# radio_r3.net
KiCad netlist of a schematic drawn in EAGLE
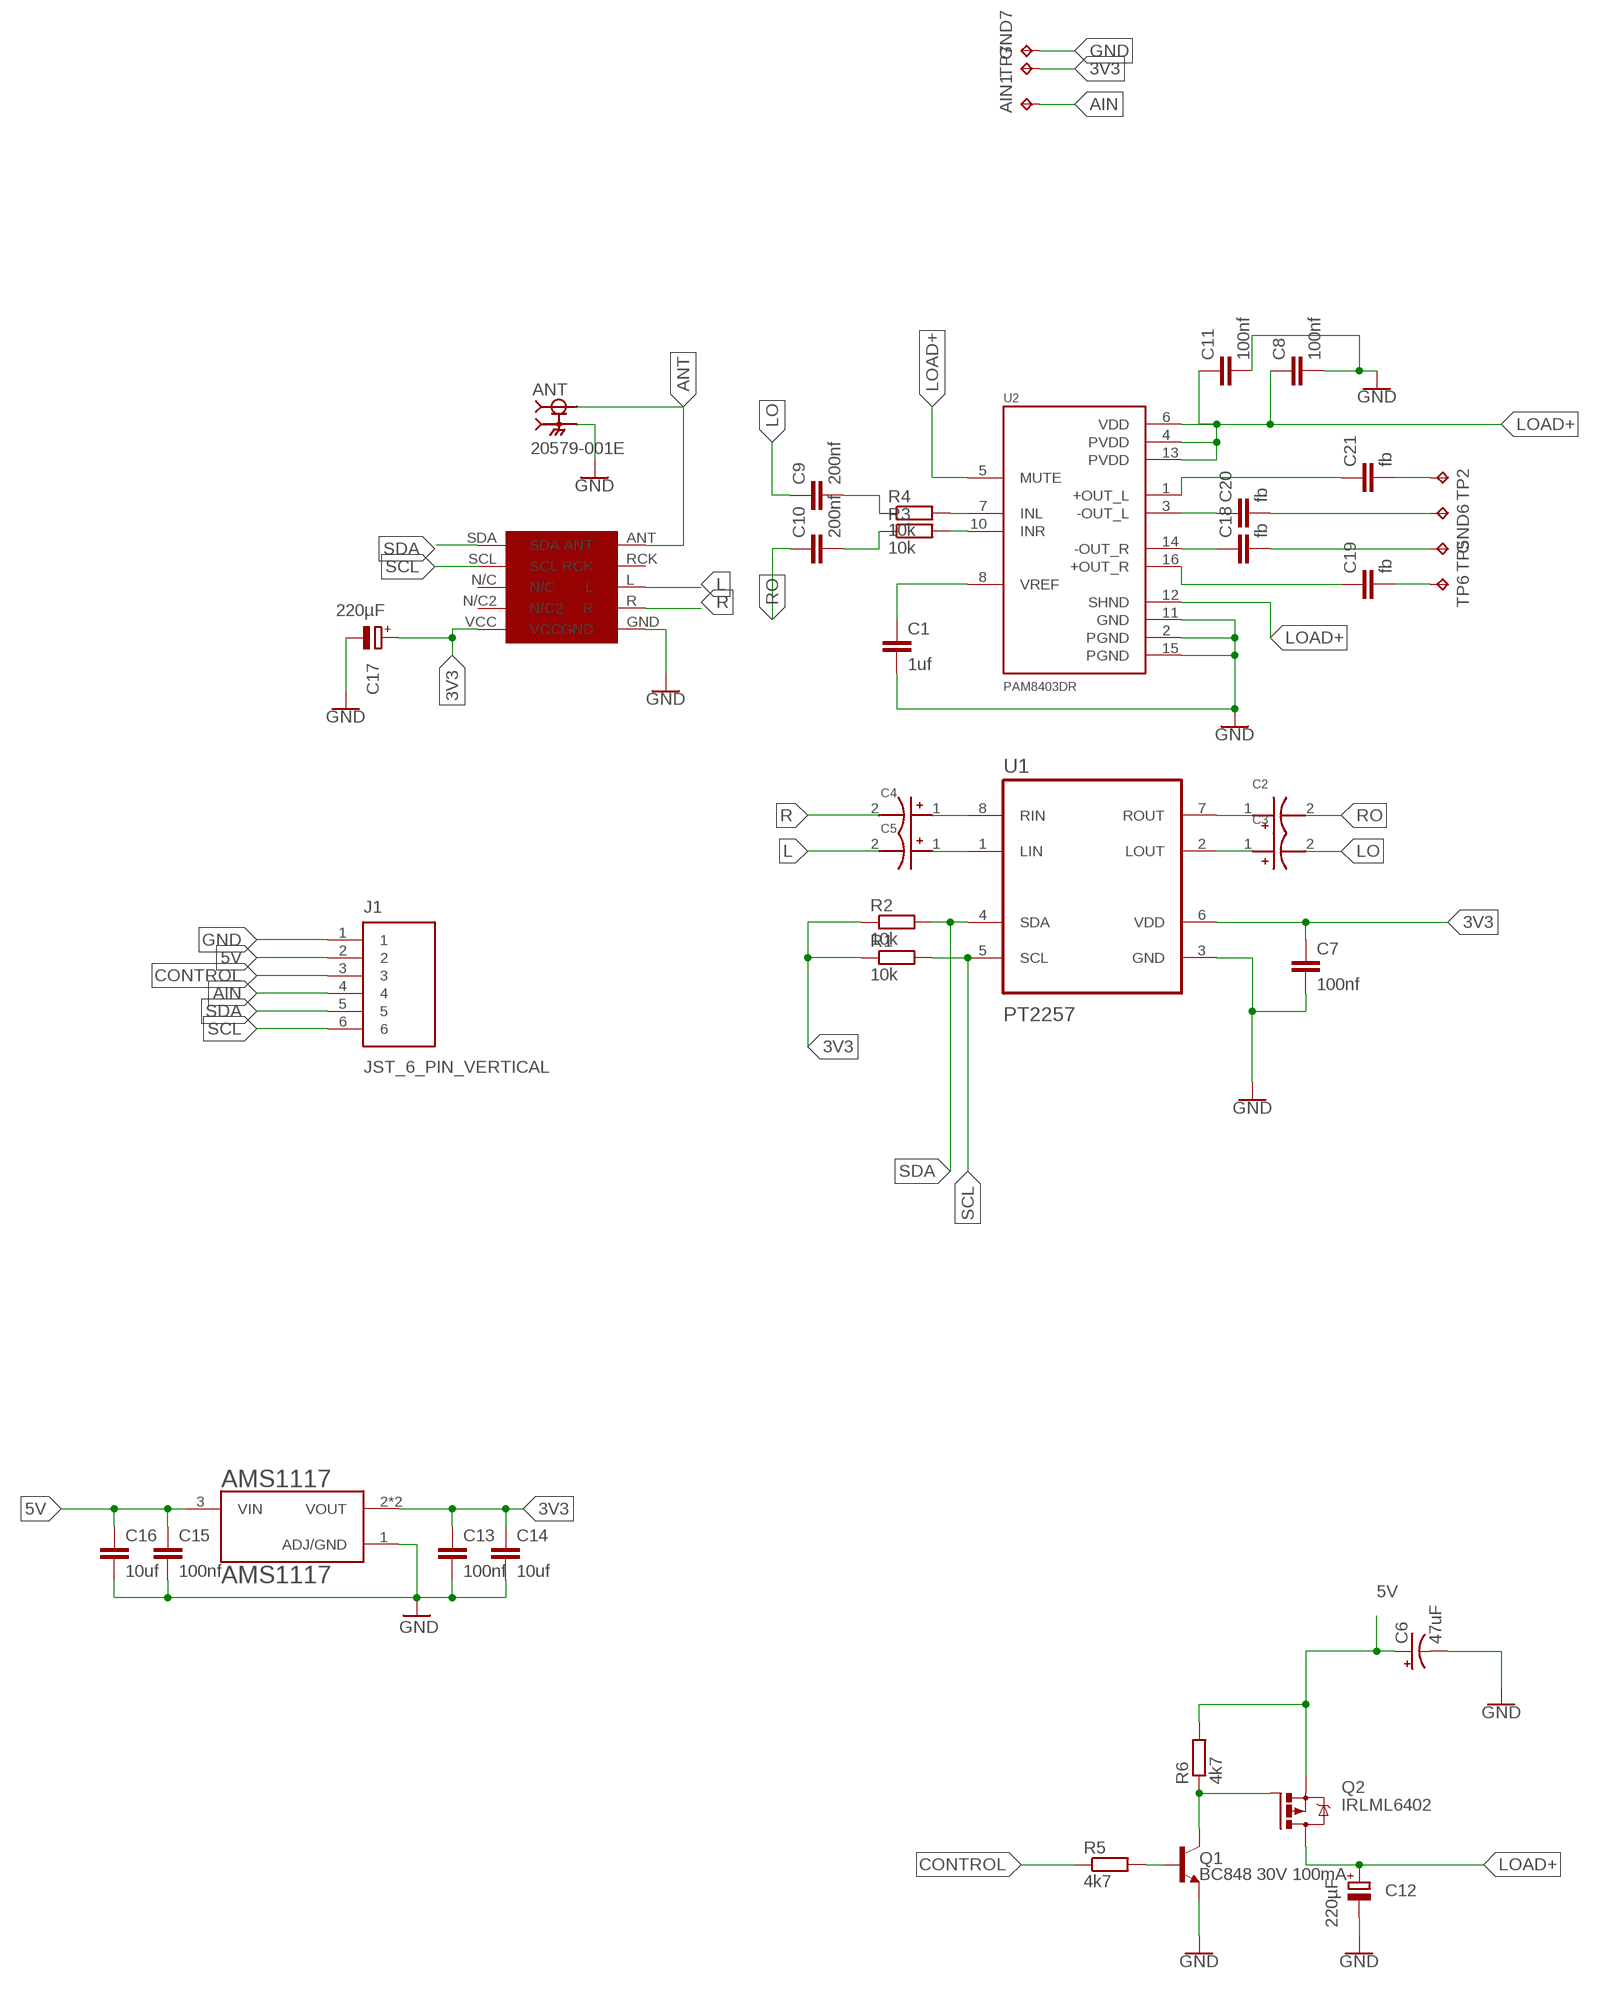
[diagram p0: schematic, sheet 1]

(export (version "E")
  (design (tool "Eeschema 10.0.6"))
  (components
    (comp (ref "AIN1")
      (value "TPTP10SQ")
      (footprint "eagle-import:TP10SQ")
      (libsource (lib "eagle-import") (part "TPTP10SQ"))
    )
    (comp (ref "AMS1117")
      (value "AMS1117")
      (footprint "eagle-import:SOT229P700X180-4N")
      (fields (field (name "MF") "Advanced Monolithic Systems"))
      (libsource (lib "eagle-import") (part "AMS1117"))
    )
    (comp (ref "ANT")
      (value "20579-001E")
      (footprint "eagle-import:IPEX_20579-001E")
      (fields (field (name "MF") "I-PEX"))
      (libsource (lib "eagle-import") (part "20579-001E"))
    )
    (comp (ref "C1")
      (value "1uf")
      (footprint "eagle-import:C0805")
      (libsource (lib "eagle-import") (part "C-EUC0805"))
    )
    (comp (ref "C2")
      (value "10uf")
      (footprint "eagle-import:CAPMP3216X180N")
      (fields (field (name "MF") "AVX") (field (name "MP") "TAJA106M010RNJ"))
      (libsource (lib "eagle-import") (part "TAJA106M010RNJ"))
    )
    (comp (ref "C3")
      (value "10uf")
      (footprint "eagle-import:CAPMP3216X180N")
      (fields (field (name "MF") "AVX") (field (name "MP") "TAJA106M010RNJ"))
      (libsource (lib "eagle-import") (part "TAJA106M010RNJ"))
    )
    (comp (ref "C4")
      (value "10uf")
      (footprint "eagle-import:CAPMP3216X180N")
      (fields (field (name "MF") "AVX") (field (name "MP") "TAJA106M010RNJ"))
      (libsource (lib "eagle-import") (part "TAJA106M010RNJ"))
    )
    (comp (ref "C5")
      (value "10uf")
      (footprint "eagle-import:CAPMP3216X180N")
      (fields (field (name "MF") "AVX") (field (name "MP") "TAJA106M010RNJ"))
      (libsource (lib "eagle-import") (part "TAJA106M010RNJ"))
    )
    (comp (ref "C6")
      (value "47uF")
      (footprint "eagle-import:EIA3528")
      (libsource (lib "eagle-import") (part "47UF-POLAR-EIA3528-10V-10%"))
    )
    (comp (ref "C7")
      (value "100nf")
      (footprint "eagle-import:C0603")
      (libsource (lib "eagle-import") (part "C-EUC0603"))
    )
    (comp (ref "C8")
      (value "100nf")
      (footprint "eagle-import:C0805")
      (libsource (lib "eagle-import") (part "C-EUC0805"))
    )
    (comp (ref "C9")
      (value "200nf")
      (footprint "eagle-import:C0805")
      (libsource (lib "eagle-import") (part "C-EUC0805"))
    )
    (comp (ref "C10")
      (value "200nf")
      (footprint "eagle-import:C0805")
      (libsource (lib "eagle-import") (part "C-EUC0805"))
    )
    (comp (ref "C11")
      (value "100nf")
      (footprint "eagle-import:C0805")
      (libsource (lib "eagle-import") (part "C-EUC0805"))
    )
    (comp (ref "C12")
      (value "220µF")
      (footprint "eagle-import:PANASONIC_D")
      (libsource (lib "eagle-import") (part "CPOL-EUD"))
    )
    (comp (ref "C13")
      (value "100nf")
      (footprint "eagle-import:C0603")
      (libsource (lib "eagle-import") (part "resistor_348_C-EUC0603"))
    )
    (comp (ref "C14")
      (value "10uf")
      (footprint "eagle-import:C0805")
      (libsource (lib "eagle-import") (part "resistor_348_C-EUC0805"))
    )
    (comp (ref "C15")
      (value "100nf")
      (footprint "eagle-import:C0603")
      (libsource (lib "eagle-import") (part "resistor_348_C-EUC0603"))
    )
    (comp (ref "C16")
      (value "10uf")
      (footprint "eagle-import:C0805")
      (libsource (lib "eagle-import") (part "resistor_348_C-EUC0805"))
    )
    (comp (ref "C17")
      (value "220µF")
      (footprint "eagle-import:PANASONIC_D")
      (libsource (lib "eagle-import") (part "CPOL-EUD"))
    )
    (comp (ref "C18")
      (value "fb")
      (footprint "eagle-import:C0805")
      (libsource (lib "eagle-import") (part "C-EUC0805"))
    )
    (comp (ref "C19")
      (value "fb")
      (footprint "eagle-import:C0805")
      (libsource (lib "eagle-import") (part "C-EUC0805"))
    )
    (comp (ref "C20")
      (value "fb")
      (footprint "eagle-import:C0805")
      (libsource (lib "eagle-import") (part "C-EUC0805"))
    )
    (comp (ref "C21")
      (value "fb")
      (footprint "eagle-import:C0805")
      (libsource (lib "eagle-import") (part "C-EUC0805"))
    )
    (comp (ref "GND6")
      (value "TPTP15R")
      (footprint "eagle-import:TP15R")
      (libsource (lib "eagle-import") (part "TPTP15R"))
    )
    (comp (ref "GND7")
      (value "TPTP10SQ")
      (footprint "eagle-import:TP10SQ")
      (libsource (lib "eagle-import") (part "TPTP10SQ"))
    )
    (comp (ref "J1")
      (value "JST_6_PIN_VERTICAL")
      (footprint "eagle-import:JST-6-SMD-VERT-1.0MM")
      (libsource (lib "eagle-import") (part "JST_6_PIN_VERTICAL"))
    )
    (comp (ref "Q1")
      (value "BC848 30V 100mA")
      (footprint "eagle-import:SOT23-3")
      (libsource (lib "eagle-import") (part "TRANS_NPN-MMBT2222AL"))
    )
    (comp (ref "Q2")
      (value "IRLML6402")
      (footprint "eagle-import:MICRO3")
      (libsource (lib "eagle-import") (part "IRLML5203"))
    )
    (comp (ref "R1")
      (value "10k")
      (footprint "eagle-import:R0603")
      (libsource (lib "eagle-import") (part "R-EU_R0603"))
    )
    (comp (ref "R2")
      (value "10k")
      (footprint "eagle-import:R0603")
      (libsource (lib "eagle-import") (part "R-EU_R0603"))
    )
    (comp (ref "R3")
      (value "10k")
      (footprint "eagle-import:R0805")
      (libsource (lib "eagle-import") (part "R-EU_R0805"))
    )
    (comp (ref "R4")
      (value "10k")
      (footprint "eagle-import:R0805")
      (libsource (lib "eagle-import") (part "R-EU_R0805"))
    )
    (comp (ref "R5")
      (value "4k7")
      (footprint "eagle-import:R0603")
      (libsource (lib "eagle-import") (part "R-EU_R0603"))
    )
    (comp (ref "R6")
      (value "4k7")
      (footprint "eagle-import:R0603")
      (libsource (lib "eagle-import") (part "R-EU_R0603"))
    )
    (comp (ref "RDA5807M")
      (value "RDA")
      (footprint "eagle-import:RDA")
      (libsource (lib "eagle-import") (part "RDA"))
    )
    (comp (ref "TP2")
      (value "TPTP15R")
      (footprint "eagle-import:TP15R")
      (libsource (lib "eagle-import") (part "TPTP15R"))
    )
    (comp (ref "TP5")
      (value "TPTP15R")
      (footprint "eagle-import:TP15R")
      (libsource (lib "eagle-import") (part "TPTP15R"))
    )
    (comp (ref "TP6")
      (value "TPTP15R")
      (footprint "eagle-import:TP15R")
      (libsource (lib "eagle-import") (part "TPTP15R"))
    )
    (comp (ref "TP7")
      (value "TPTP10SQ")
      (footprint "eagle-import:TP10SQ")
      (libsource (lib "eagle-import") (part "TPTP10SQ"))
    )
    (comp (ref "U1")
      (value "PT2257")
      (footprint "eagle-import:SOIC127P600X175-8N")
      (fields (field (name "MF") "Texas Instruments") (field (name "MP") "NE555PS"))
      (libsource (lib "eagle-import") (part "PT2257"))
    )
    (comp (ref "U2")
      (value "PAM8403DR")
      (footprint "eagle-import:SOIC127P605X150-16N")
      (fields (field (name "MF") "Diodes Inc."))
      (libsource (lib "eagle-import") (part "PAM8403DR"))
    )
  )
  (nets
    (net (code "1") (name "3V3") (class "Default")
      (node (ref "AMS1117") (pin "2") (pinfunction "VOUT_2") (pintype "output"))
      (node (ref "AMS1117") (pin "4") (pinfunction "VOUT_4") (pintype "output"))
      (node (ref "C13") (pin "1") (pinfunction "1_1") (pintype "passive"))
      (node (ref "C14") (pin "1") (pinfunction "1_1") (pintype "passive"))
      (node (ref "C17") (pin "+") (pinfunction "+_+") (pintype "passive"))
      (node (ref "C7") (pin "1") (pinfunction "1_1") (pintype "passive"))
      (node (ref "R1") (pin "1") (pinfunction "1_1") (pintype "passive"))
      (node (ref "R2") (pin "1") (pinfunction "1_1") (pintype "passive"))
      (node (ref "RDA5807M") (pin "VCC") (pinfunction "VCC_VCC") (pintype "power_in"))
      (node (ref "TP7") (pin "TP") (pinfunction "TP_TP") (pintype "input"))
      (node (ref "U1") (pin "6") (pinfunction "VDD_6") (pintype "bidirectional"))
    )
    (net (code "2") (name "5V") (class "Default")
      (node (ref "AMS1117") (pin "3") (pinfunction "VIN_3") (pintype "input"))
      (node (ref "C15") (pin "1") (pinfunction "1_1") (pintype "passive"))
      (node (ref "C16") (pin "1") (pinfunction "1_1") (pintype "passive"))
      (node (ref "C6") (pin "A") (pinfunction "+_A") (pintype "passive"))
      (node (ref "J1") (pin "2") (pinfunction "2_2") (pintype "bidirectional"))
      (node (ref "Q2") (pin "2") (pinfunction "S_2") (pintype "passive"))
      (node (ref "R6") (pin "2") (pinfunction "2_2") (pintype "passive"))
    )
    (net (code "3") (name "AIN") (class "Default")
      (node (ref "AIN1") (pin "TP") (pinfunction "TP_TP") (pintype "input"))
      (node (ref "J1") (pin "4") (pinfunction "4_4") (pintype "bidirectional"))
    )
    (net (code "4") (name "ANT") (class "Default")
      (node (ref "ANT") (pin "1") (pinfunction "SIGNAL_1") (pintype "passive"))
      (node (ref "RDA5807M") (pin "ANT") (pinfunction "ANT_ANT") (pintype "input"))
    )
    (net (code "5") (name "CONTROL") (class "Default")
      (node (ref "J1") (pin "3") (pinfunction "3_3") (pintype "bidirectional"))
      (node (ref "R5") (pin "1") (pinfunction "1_1") (pintype "passive"))
    )
    (net (code "6") (name "GND") (class "Default")
      (node (ref "AMS1117") (pin "1") (pinfunction "ADJ/GND_1") (pintype "power_in"))
      (node (ref "ANT") (pin "G1") (pinfunction "GROUND_G1") (pintype "passive"))
      (node (ref "ANT") (pin "G2") (pinfunction "GROUND_G2") (pintype "passive"))
      (node (ref "ANT") (pin "G3") (pinfunction "GROUND_G3") (pintype "passive"))
      (node (ref "C1") (pin "2") (pinfunction "2_2") (pintype "passive"))
      (node (ref "C11") (pin "2") (pinfunction "2_2") (pintype "passive"))
      (node (ref "C12") (pin "-") (pinfunction "-_-") (pintype "passive"))
      (node (ref "C13") (pin "2") (pinfunction "2_2") (pintype "passive"))
      (node (ref "C14") (pin "2") (pinfunction "2_2") (pintype "passive"))
      (node (ref "C15") (pin "2") (pinfunction "2_2") (pintype "passive"))
      (node (ref "C16") (pin "2") (pinfunction "2_2") (pintype "passive"))
      (node (ref "C17") (pin "-") (pinfunction "-_-") (pintype "passive"))
      (node (ref "C6") (pin "C") (pinfunction "-_C") (pintype "passive"))
      (node (ref "C7") (pin "2") (pinfunction "2_2") (pintype "passive"))
      (node (ref "C8") (pin "2") (pinfunction "2_2") (pintype "passive"))
      (node (ref "GND7") (pin "TP") (pinfunction "TP_TP") (pintype "input"))
      (node (ref "J1") (pin "1") (pinfunction "1_1") (pintype "bidirectional"))
      (node (ref "Q1") (pin "2") (pinfunction "E_2") (pintype "passive"))
      (node (ref "RDA5807M") (pin "GND") (pinfunction "GND_GND") (pintype "power_in"))
      (node (ref "U1") (pin "3") (pinfunction "GND_3") (pintype "output"))
      (node (ref "U2") (pin "11") (pinfunction "GND_11") (pintype "power_in"))
      (node (ref "U2") (pin "15") (pinfunction "PGND_15") (pintype "power_in"))
      (node (ref "U2") (pin "2") (pinfunction "PGND_2") (pintype "power_in"))
    )
    (net (code "7") (name "L") (class "Default")
      (node (ref "C5") (pin "2") (pinfunction "2_2") (pintype "passive"))
      (node (ref "RDA5807M") (pin "L") (pinfunction "L_L") (pintype "output"))
    )
    (net (code "8") (name "LO") (class "Default")
      (node (ref "C3") (pin "2") (pinfunction "2_2") (pintype "passive"))
      (node (ref "C9") (pin "1") (pinfunction "1_1") (pintype "passive"))
    )
    (net (code "9") (name "LOAD+") (class "Default")
      (node (ref "C11") (pin "1") (pinfunction "1_1") (pintype "passive"))
      (node (ref "C12") (pin "+") (pinfunction "+_+") (pintype "passive"))
      (node (ref "C8") (pin "1") (pinfunction "1_1") (pintype "passive"))
      (node (ref "Q2") (pin "3") (pinfunction "D_3") (pintype "passive"))
      (node (ref "U2") (pin "12") (pinfunction "SHND_12") (pintype "power_in"))
      (node (ref "U2") (pin "13") (pinfunction "PVDD_13") (pintype "power_in"))
      (node (ref "U2") (pin "4") (pinfunction "PVDD_4") (pintype "power_in"))
      (node (ref "U2") (pin "5") (pinfunction "MUTE_5") (pintype "input"))
      (node (ref "U2") (pin "6") (pinfunction "VDD_6") (pintype "power_in"))
    )
    (net (code "10") (name "Net-(C9-Pad2)") (class "Default")
      (node (ref "C9") (pin "2") (pinfunction "2_2") (pintype "passive"))
      (node (ref "R4") (pin "1") (pinfunction "1_1") (pintype "passive"))
    )
    (net (code "11") (name "Net-(C10-Pad2)") (class "Default")
      (node (ref "C10") (pin "2") (pinfunction "2_2") (pintype "passive"))
      (node (ref "R3") (pin "1") (pinfunction "1_1") (pintype "passive"))
    )
    (net (code "12") (name "Net-(C18-Pad2)") (class "Default")
      (node (ref "C18") (pin "2") (pinfunction "2_2") (pintype "passive"))
      (node (ref "TP5") (pin "TP") (pinfunction "TP_TP") (pintype "input"))
    )
    (net (code "13") (name "Net-(C19-Pad2)") (class "Default")
      (node (ref "C19") (pin "2") (pinfunction "2_2") (pintype "passive"))
      (node (ref "TP6") (pin "TP") (pinfunction "TP_TP") (pintype "input"))
    )
    (net (code "14") (name "Net-(C20-Pad2)") (class "Default")
      (node (ref "C20") (pin "2") (pinfunction "2_2") (pintype "passive"))
      (node (ref "GND6") (pin "TP") (pinfunction "TP_TP") (pintype "input"))
    )
    (net (code "15") (name "Net-(C21-Pad2)") (class "Default")
      (node (ref "C21") (pin "2") (pinfunction "2_2") (pintype "passive"))
      (node (ref "TP2") (pin "TP") (pinfunction "TP_TP") (pintype "input"))
    )
    (net (code "16") (name "Net-(Q1-B)") (class "Default")
      (node (ref "Q1") (pin "1") (pinfunction "B_1") (pintype "passive"))
      (node (ref "R5") (pin "2") (pinfunction "2_2") (pintype "passive"))
    )
    (net (code "17") (name "Net-(Q1-C)") (class "Default")
      (node (ref "Q1") (pin "3") (pinfunction "C_3") (pintype "passive"))
      (node (ref "Q2") (pin "1") (pinfunction "G_1") (pintype "passive"))
      (node (ref "R6") (pin "1") (pinfunction "1_1") (pintype "passive"))
    )
    (net (code "18") (name "Net-(U1-LIN)") (class "Default")
      (node (ref "C5") (pin "1") (pinfunction "1_1") (pintype "passive"))
      (node (ref "U1") (pin "1") (pinfunction "LIN_1") (pintype "power_in"))
    )
    (net (code "19") (name "Net-(U1-LOUT)") (class "Default")
      (node (ref "C3") (pin "1") (pinfunction "1_1") (pintype "passive"))
      (node (ref "U1") (pin "2") (pinfunction "LOUT_2") (pintype "bidirectional"))
    )
    (net (code "20") (name "Net-(U1-RIN)") (class "Default")
      (node (ref "C4") (pin "1") (pinfunction "1_1") (pintype "passive"))
      (node (ref "U1") (pin "8") (pinfunction "RIN_8") (pintype "power_in"))
    )
    (net (code "21") (name "Net-(U1-ROUT)") (class "Default")
      (node (ref "C2") (pin "1") (pinfunction "1_1") (pintype "passive"))
      (node (ref "U1") (pin "7") (pinfunction "ROUT_7") (pintype "bidirectional"))
    )
    (net (code "22") (name "Net-(U2-+OUT_L)") (class "Default")
      (node (ref "C21") (pin "1") (pinfunction "1_1") (pintype "passive"))
      (node (ref "U2") (pin "1") (pinfunction "+OUT_L_1") (pintype "output"))
    )
    (net (code "23") (name "Net-(U2-+OUT_R)") (class "Default")
      (node (ref "C19") (pin "1") (pinfunction "1_1") (pintype "passive"))
      (node (ref "U2") (pin "16") (pinfunction "+OUT_R_16") (pintype "output"))
    )
    (net (code "24") (name "Net-(U2--OUT_L)") (class "Default")
      (node (ref "C20") (pin "1") (pinfunction "1_1") (pintype "passive"))
      (node (ref "U2") (pin "3") (pinfunction "-OUT_L_3") (pintype "output"))
    )
    (net (code "25") (name "Net-(U2--OUT_R)") (class "Default")
      (node (ref "C18") (pin "1") (pinfunction "1_1") (pintype "passive"))
      (node (ref "U2") (pin "14") (pinfunction "-OUT_R_14") (pintype "output"))
    )
    (net (code "26") (name "Net-(U2-INL)") (class "Default")
      (node (ref "R4") (pin "2") (pinfunction "2_2") (pintype "passive"))
      (node (ref "U2") (pin "7") (pinfunction "INL_7") (pintype "input"))
    )
    (net (code "27") (name "Net-(U2-INR)") (class "Default")
      (node (ref "R3") (pin "2") (pinfunction "2_2") (pintype "passive"))
      (node (ref "U2") (pin "10") (pinfunction "INR_10") (pintype "input"))
    )
    (net (code "28") (name "Net-(U2-VREF)") (class "Default")
      (node (ref "C1") (pin "1") (pinfunction "1_1") (pintype "passive"))
      (node (ref "U2") (pin "8") (pinfunction "VREF_8") (pintype "input"))
    )
    (net (code "29") (name "R") (class "Default")
      (node (ref "C4") (pin "2") (pinfunction "2_2") (pintype "passive"))
      (node (ref "RDA5807M") (pin "R") (pinfunction "R_R") (pintype "output"))
    )
    (net (code "30") (name "RO") (class "Default")
      (node (ref "C10") (pin "1") (pinfunction "1_1") (pintype "passive"))
      (node (ref "C2") (pin "2") (pinfunction "2_2") (pintype "passive"))
    )
    (net (code "31") (name "SCL") (class "Default")
      (node (ref "J1") (pin "6") (pinfunction "6_6") (pintype "bidirectional"))
      (node (ref "R1") (pin "2") (pinfunction "2_2") (pintype "passive"))
      (node (ref "RDA5807M") (pin "SCL") (pinfunction "SCL_SCL") (pintype "bidirectional"))
      (node (ref "U1") (pin "5") (pinfunction "SCL_5") (pintype "bidirectional"))
    )
    (net (code "32") (name "SDA") (class "Default")
      (node (ref "J1") (pin "5") (pinfunction "5_5") (pintype "bidirectional"))
      (node (ref "R2") (pin "2") (pinfunction "2_2") (pintype "passive"))
      (node (ref "RDA5807M") (pin "SDA") (pinfunction "SDA_SDA") (pintype "bidirectional"))
      (node (ref "U1") (pin "4") (pinfunction "SDA_4") (pintype "bidirectional"))
    )
    (net (code "33") (name "unconnected-(RDA5807M-PadN{slash}C)") (class "Default")
      (node (ref "RDA5807M") (pin "N/C") (pinfunction "N/C_N/C") (pintype "passive"))
    )
    (net (code "34") (name "unconnected-(RDA5807M-PadN{slash}C2)") (class "Default")
      (node (ref "RDA5807M") (pin "N/C2") (pinfunction "N/C2_N/C2") (pintype "passive"))
    )
    (net (code "35") (name "unconnected-(RDA5807M-PadRCK)") (class "Default")
      (node (ref "RDA5807M") (pin "RCK") (pinfunction "RCK_RCK") (pintype "bidirectional"))
    )
  )
)
